# Connectors.net
KiCad netlist of a schematic drawn in Altium Designer
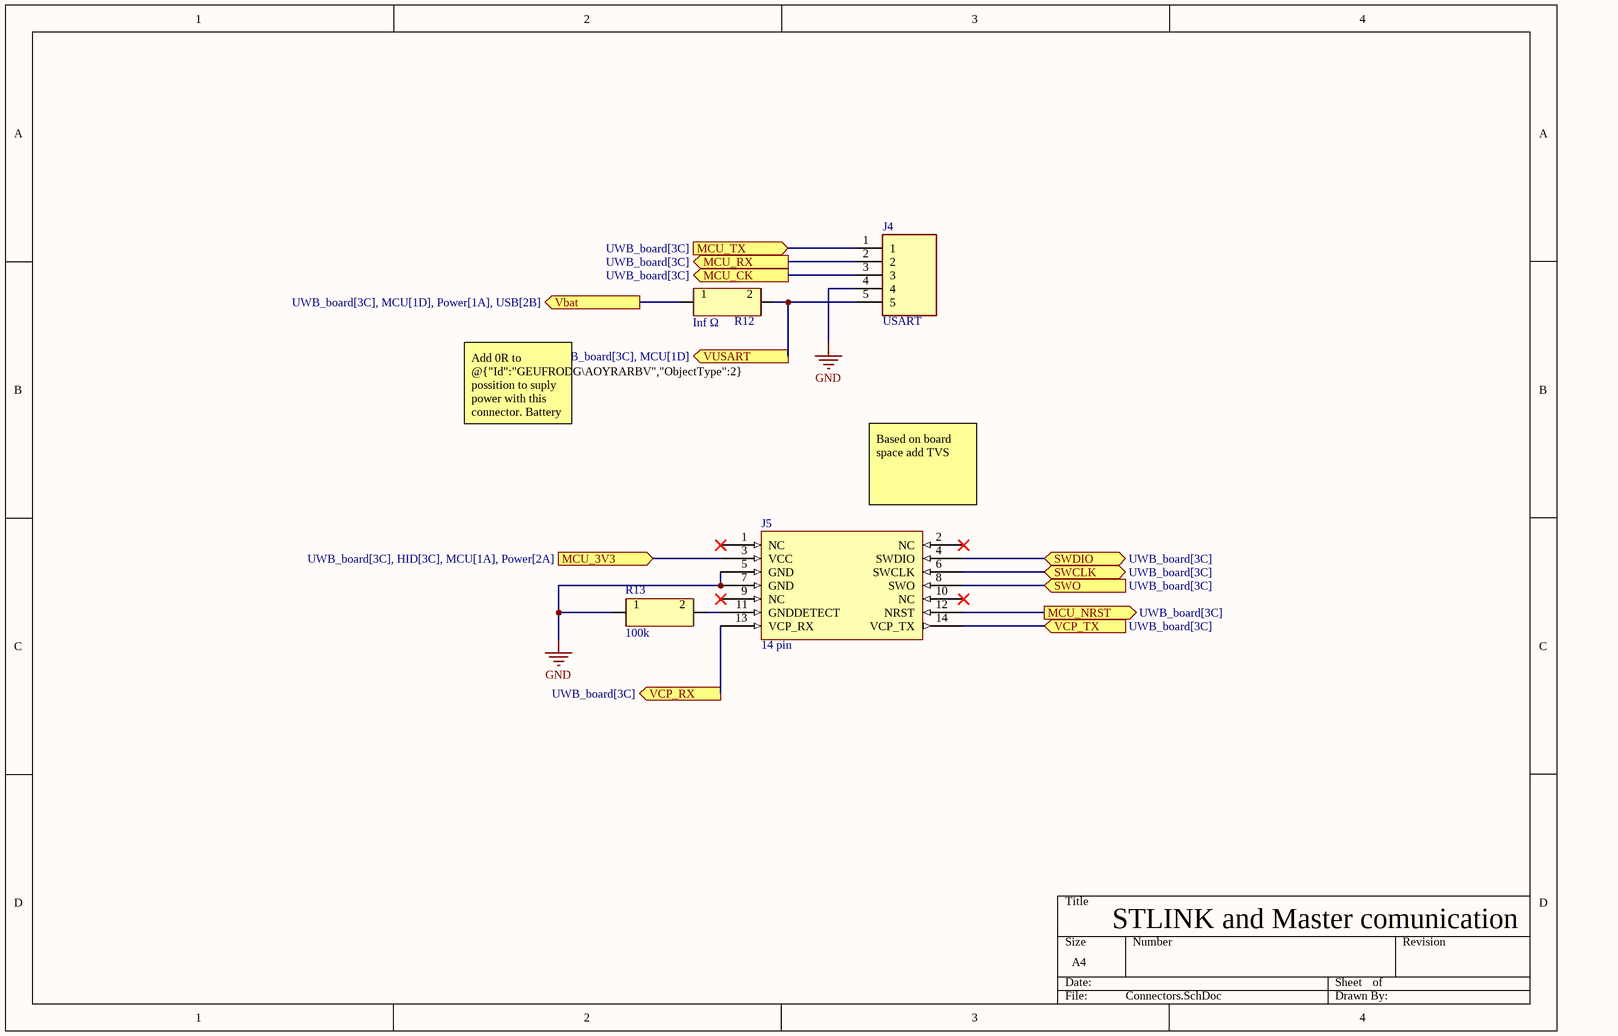
[diagram p0: Connectors.SchDoc]

(export (version "E")
  (design (tool "Eeschema 10.0.6"))
  (components
    (comp (ref "J4")
      (value "USART")
      (footprint "JST_B5B-XH-A")
      (description "comunication to master")
      (libsource (lib "Schlib1") (part "S5B-XH-A_LF__SN_"))
    )
    (comp (ref "J5")
      (value "14 pin")
      (footprint "FTSH14")
      (description "For SWD debug")
      (libsource (lib "Schlib1") (part "FTSH-107-01-LM-DV-K"))
    )
    (comp (ref "R12")
      (value "Inf Ω")
      (footprint "0603_empty")
      (description "empty space for 0603 device")
      (fields (field (name "LCSC PART #") "None") (field (name "Comment") "Empty 0603"))
      (libsource (lib "Schlib1") (part "0603_empty"))
    )
    (comp (ref "R13")
      (value "100k")
      (footprint "0603_res")
      (fields (field (name "LCSC PART #") "C25803"))
      (libsource (lib "Schlib1") (part "0603WAF1003T5E"))
    )
  )
  (nets
    (net (code "1") (name "/MCU_3V3") (class "Default")
      (node (ref "J5") (pin "3") (pinfunction "VCC_3") (pintype "input"))
    )
    (net (code "2") (name "/MCU_CK") (class "Default")
      (node (ref "J4") (pin "3") (pinfunction "3_3") (pintype "passive"))
    )
    (net (code "3") (name "/MCU_NRST") (class "Default")
      (node (ref "J5") (pin "12") (pinfunction "NRST_12") (pintype "input"))
    )
    (net (code "4") (name "/MCU_RX") (class "Default")
      (node (ref "J4") (pin "2") (pinfunction "2_2") (pintype "passive"))
    )
    (net (code "5") (name "/MCU_TX") (class "Default")
      (node (ref "J4") (pin "1") (pinfunction "1_1") (pintype "passive"))
    )
    (net (code "6") (name "/SWCLK") (class "Default")
      (node (ref "J5") (pin "6") (pinfunction "SWCLK_6") (pintype "input"))
    )
    (net (code "7") (name "/SWDIO") (class "Default")
      (node (ref "J5") (pin "4") (pinfunction "SWDIO_4") (pintype "input"))
    )
    (net (code "8") (name "/SWO") (class "Default")
      (node (ref "J5") (pin "8") (pinfunction "SWO_8") (pintype "input"))
    )
    (net (code "9") (name "/VCP_RX") (class "Default")
      (node (ref "J5") (pin "13") (pinfunction "VCP_RX_13") (pintype "input"))
    )
    (net (code "10") (name "/VCP_TX") (class "Default")
      (node (ref "J5") (pin "14") (pinfunction "VCP_TX_14") (pintype "output"))
    )
    (net (code "11") (name "/VUSART") (class "Default")
      (node (ref "J4") (pin "5") (pinfunction "5_5") (pintype "passive"))
      (node (ref "R12") (pin "2") (pinfunction "3_2") (pintype "passive"))
    )
    (net (code "12") (name "/Vbat") (class "Default")
      (node (ref "R12") (pin "1") (pinfunction "1_1") (pintype "passive"))
    )
    (net (code "13") (name "GND") (class "Default")
      (node (ref "J4") (pin "4") (pinfunction "4_4") (pintype "passive"))
      (node (ref "J5") (pin "5") (pinfunction "GND_5") (pintype "input"))
      (node (ref "J5") (pin "7") (pinfunction "GND_7") (pintype "input"))
      (node (ref "R13") (pin "1") (pinfunction "1_1") (pintype "passive"))
    )
    (net (code "14") (name "Net-(J5-GNDDETECT)") (class "Default")
      (node (ref "J5") (pin "11") (pinfunction "GNDDETECT_11") (pintype "input"))
      (node (ref "R13") (pin "2") (pinfunction "3_2") (pintype "passive"))
    )
    (net (code "15") (name "unconnected-(J5-NC-Pad1)") (class "Default")
      (node (ref "J5") (pin "1") (pinfunction "NC_1") (pintype "input+no_connect"))
    )
    (net (code "16") (name "unconnected-(J5-NC-Pad2)") (class "Default")
      (node (ref "J5") (pin "2") (pinfunction "NC_2") (pintype "input+no_connect"))
    )
    (net (code "17") (name "unconnected-(J5-NC-Pad9)") (class "Default")
      (node (ref "J5") (pin "9") (pinfunction "NC_9") (pintype "input+no_connect"))
    )
    (net (code "18") (name "unconnected-(J5-NC-Pad10)") (class "Default")
      (node (ref "J5") (pin "10") (pinfunction "NC_10") (pintype "input+no_connect"))
    )
  )
)
